# main.net
KiCad netlist of a schematic drawn in EAGLE
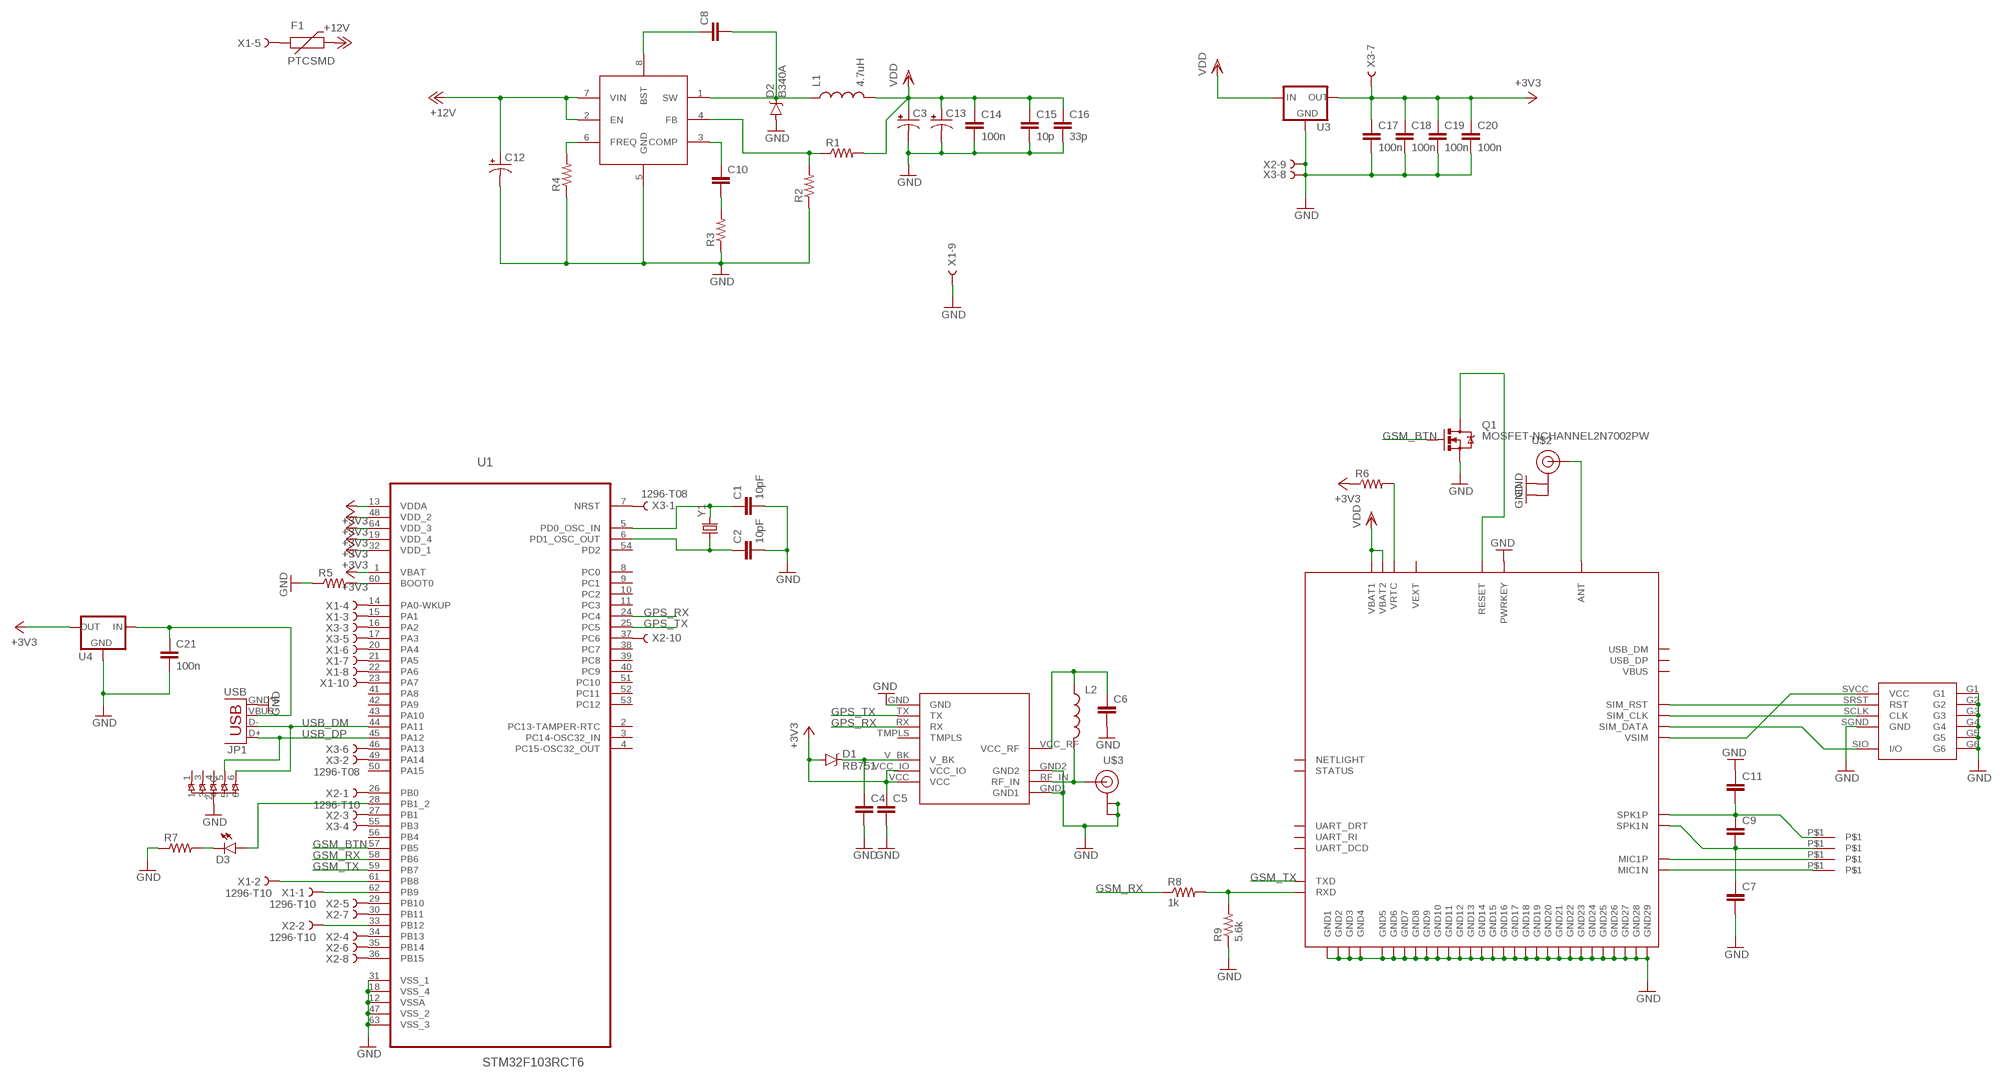
[diagram p0: schematic, sheet 1]

(export (version "E")
  (design (tool "Eeschema 10.0.6"))
  (components
    (comp (ref "C1")
      (value "10pF")
      (footprint "eagle-import:0603-CAP")
      (libsource (lib "eagle-import") (part "10PF-50V-5%(0603)"))
    )
    (comp (ref "C2")
      (value "10pF")
      (footprint "eagle-import:0603-CAP")
      (libsource (lib "eagle-import") (part "10PF-50V-5%(0603)"))
    )
    (comp (ref "C3")
      (value "CAP_POL6032")
      (footprint "eagle-import:EIA6032")
      (libsource (lib "eagle-import") (part "CAP_POL6032"))
    )
    (comp (ref "C4")
      (value "CAP1210")
      (footprint "eagle-import:1210")
      (libsource (lib "eagle-import") (part "CAP1210"))
    )
    (comp (ref "C5")
      (value "CAP1210")
      (footprint "eagle-import:1210")
      (libsource (lib "eagle-import") (part "CAP1210"))
    )
    (comp (ref "C6")
      (value "CAP0402-CAP")
      (footprint "eagle-import:0402-CAP")
      (libsource (lib "eagle-import") (part "SparkFun-Passives_CAP0402-CAP"))
    )
    (comp (ref "C7")
      (value "CAP0402-CAP")
      (footprint "eagle-import:0402-CAP")
      (libsource (lib "eagle-import") (part "SparkFun-Passives_CAP0402-CAP"))
    )
    (comp (ref "C8")
      (value "CAP0805")
      (footprint "eagle-import:0805")
      (libsource (lib "eagle-import") (part "SparkFun-Passives_CAP0805"))
    )
    (comp (ref "C9")
      (value "CAP0402-CAP")
      (footprint "eagle-import:0402-CAP")
      (libsource (lib "eagle-import") (part "SparkFun-Passives_CAP0402-CAP"))
    )
    (comp (ref "C10")
      (value "CAP0402-CAP")
      (footprint "eagle-import:0402-CAP")
      (libsource (lib "eagle-import") (part "SparkFun-Passives_CAP0402-CAP"))
    )
    (comp (ref "C11")
      (value "CAP0402-CAP")
      (footprint "eagle-import:0402-CAP")
      (libsource (lib "eagle-import") (part "SparkFun-Passives_CAP0402-CAP"))
    )
    (comp (ref "C12")
      (value "CPOL-USSMCC")
      (footprint "eagle-import:SMC_C")
      (libsource (lib "eagle-import") (part "CPOL-USSMCC"))
    )
    (comp (ref "C13")
      (value "CAP_POL6032")
      (footprint "eagle-import:EIA6032")
      (libsource (lib "eagle-import") (part "CAP_POL6032"))
    )
    (comp (ref "C14")
      (value "100n")
      (footprint "eagle-import:0805")
      (libsource (lib "eagle-import") (part "SparkFun-Passives_CAP0805"))
    )
    (comp (ref "C15")
      (value "10p")
      (footprint "eagle-import:0402-CAP")
      (libsource (lib "eagle-import") (part "SparkFun-Passives_CAP0402-CAP"))
    )
    (comp (ref "C16")
      (value "33p")
      (footprint "eagle-import:0402-CAP")
      (libsource (lib "eagle-import") (part "SparkFun-Passives_CAP0402-CAP"))
    )
    (comp (ref "C17")
      (value "100n")
      (footprint "eagle-import:0805")
      (libsource (lib "eagle-import") (part "SparkFun-Passives_CAP0805"))
    )
    (comp (ref "C18")
      (value "100n")
      (footprint "eagle-import:0805")
      (libsource (lib "eagle-import") (part "SparkFun-Passives_CAP0805"))
    )
    (comp (ref "C19")
      (value "100n")
      (footprint "eagle-import:0805")
      (libsource (lib "eagle-import") (part "SparkFun-Passives_CAP0805"))
    )
    (comp (ref "C20")
      (value "100n")
      (footprint "eagle-import:0805")
      (libsource (lib "eagle-import") (part "SparkFun-Passives_CAP0805"))
    )
    (comp (ref "C21")
      (value "100n")
      (footprint "eagle-import:0805")
      (libsource (lib "eagle-import") (part "SparkFun-Passives_CAP0805"))
    )
    (comp (ref "D1")
      (value "RB751")
      (footprint "eagle-import:SOD-523")
      (libsource (lib "eagle-import") (part "DIODE-SCHOTTKY-RB751"))
    )
    (comp (ref "D2")
      (value "B340A")
      (footprint "eagle-import:SMA-DIODE")
      (libsource (lib "eagle-import") (part "DIODE-SCHOTTKY-B340A"))
    )
    (comp (ref "D3")
      (value "LED0603")
      (footprint "eagle-import:LED-0603")
      (libsource (lib "eagle-import") (part "LED0603"))
    )
    (comp (ref "F1")
      (value "PTCSMD")
      (footprint "eagle-import:PTC-1206")
      (libsource (lib "eagle-import") (part "PTCSMD"))
    )
    (comp (ref "JP1")
      (value "USB")
      (footprint "eagle-import:USB-MICROB-2")
      (libsource (lib "eagle-import") (part "USB"))
    )
    (comp (ref "L1")
      (value "4.7uH")
      (footprint "eagle-import:CR75")
      (libsource (lib "eagle-import") (part "INDUCTOR68UH-1A"))
    )
    (comp (ref "L2")
      (value "INDUCTOR0402")
      (footprint "eagle-import:C0402")
      (libsource (lib "eagle-import") (part "INDUCTOR0402"))
    )
    (comp (ref "Q1")
      (value "MOSFET-NCHANNEL2N7002PW")
      (footprint "eagle-import:SOT323")
      (libsource (lib "eagle-import") (part "MOSFET-NCHANNEL2N7002PW"))
    )
    (comp (ref "R1")
      (value "RESISTOR0402-RES")
      (footprint "eagle-import:0402-RES")
      (libsource (lib "eagle-import") (part "RESISTOR0402-RES"))
    )
    (comp (ref "R2")
      (value "RESISTOR0402-RES")
      (footprint "eagle-import:0402-RES")
      (libsource (lib "eagle-import") (part "RESISTOR0402-RES"))
    )
    (comp (ref "R3")
      (value "RESISTOR0402-RES")
      (footprint "eagle-import:0402-RES")
      (libsource (lib "eagle-import") (part "RESISTOR0402-RES"))
    )
    (comp (ref "R4")
      (value "RESISTOR0402-RES")
      (footprint "eagle-import:0402-RES")
      (libsource (lib "eagle-import") (part "RESISTOR0402-RES"))
    )
    (comp (ref "R5")
      (value "RESISTOR0402-RES")
      (footprint "eagle-import:0402-RES")
      (libsource (lib "eagle-import") (part "RESISTOR0402-RES"))
    )
    (comp (ref "R6")
      (value "RESISTOR0402-RES")
      (footprint "eagle-import:0402-RES")
      (libsource (lib "eagle-import") (part "RESISTOR0402-RES"))
    )
    (comp (ref "R7")
      (value "RESISTOR0402-RES")
      (footprint "eagle-import:0402-RES")
      (libsource (lib "eagle-import") (part "RESISTOR0402-RES"))
    )
    (comp (ref "R8")
      (value "1k")
      (footprint "eagle-import:0402-RES")
      (libsource (lib "eagle-import") (part "RESISTOR0402-RES"))
    )
    (comp (ref "R9")
      (value "5.6k")
      (footprint "eagle-import:0402-RES")
      (libsource (lib "eagle-import") (part "RESISTOR0402-RES"))
    )
    (comp (ref "U$1")
      (value "SIM800_MIN")
      (footprint "eagle-import:SIM800_MIN")
      (libsource (lib "eagle-import") (part "SIM800_MIN"))
    )
    (comp (ref "U$2")
      (value "U.FL")
      (footprint "eagle-import:U.FL2")
      (libsource (lib "eagle-import") (part "U.FL"))
    )
    (comp (ref "U$3")
      (value "U.FL")
      (footprint "eagle-import:U.FL2")
      (libsource (lib "eagle-import") (part "U.FL"))
    )
    (comp (ref "U$4")
      (value "VK_GPS_U7_MIN")
      (footprint "eagle-import:VK_GPS_U7_MIN")
      (libsource (lib "eagle-import") (part "VK_GPS_U7_MIN"))
    )
    (comp (ref "U$7")
      (value "SIM_NOVPP")
      (footprint "eagle-import:WURTH_NANO_SIM_NOVPP")
      (libsource (lib "eagle-import") (part "SIM_NOVPP"))
    )
    (comp (ref "U$8")
      (value "PAD1")
      (footprint "eagle-import:PAD1")
      (libsource (lib "eagle-import") (part "PAD1"))
    )
    (comp (ref "U$9")
      (value "PAD1")
      (footprint "eagle-import:PAD1")
      (libsource (lib "eagle-import") (part "PAD1"))
    )
    (comp (ref "U$13")
      (value "PAD1")
      (footprint "eagle-import:PAD1")
      (libsource (lib "eagle-import") (part "PAD1"))
    )
    (comp (ref "U$14")
      (value "PAD1")
      (footprint "eagle-import:PAD1")
      (libsource (lib "eagle-import") (part "PAD1"))
    )
    (comp (ref "U1")
      (value "STM32F103RCT6")
      (footprint "eagle-import:QFP50P1200X1200X160-64N")
      (libsource (lib "eagle-import") (part "STM32F103RCT6"))
    )
    (comp (ref "U2")
      (value "MP1584")
      (footprint "eagle-import:SO8")
      (libsource (lib "eagle-import") (part "MP1584"))
    )
    (comp (ref "U3")
      (value "XC63FPM")
      (footprint "eagle-import:SOT23")
      (libsource (lib "eagle-import") (part "XC63FPM"))
    )
    (comp (ref "U4")
      (value "XC63FPM")
      (footprint "eagle-import:SOT23")
      (libsource (lib "eagle-import") (part "XC63FPM"))
    )
    (comp (ref "U5")
      (value "SMF05C")
      (footprint "eagle-import:SC70-6L")
      (libsource (lib "eagle-import") (part "SMF05C"))
    )
    (comp (ref "X1")
      (value "1296-T10")
      (footprint "eagle-import:1296-10")
      (libsource (lib "eagle-import") (part "1296-T10"))
    )
    (comp (ref "X2")
      (value "1296-T10")
      (footprint "eagle-import:1296-10")
      (libsource (lib "eagle-import") (part "1296-T10"))
    )
    (comp (ref "X3")
      (value "1296-T08")
      (footprint "eagle-import:1296-08")
      (libsource (lib "eagle-import") (part "1296-T08"))
    )
    (comp (ref "Y1")
      (value "CRYSTAL5X3")
      (footprint "eagle-import:CRYSTAL-SMD-5X3")
      (libsource (lib "eagle-import") (part "CRYSTAL5X3"))
    )
  )
  (nets
    (net (code "1") (name "+3V3") (class "Default")
      (node (ref "C17") (pin "1") (pinfunction "1_1") (pintype "passive"))
      (node (ref "C18") (pin "1") (pinfunction "1_1") (pintype "passive"))
      (node (ref "C19") (pin "1") (pinfunction "1_1") (pintype "passive"))
      (node (ref "C20") (pin "1") (pinfunction "1_1") (pintype "passive"))
      (node (ref "C5") (pin "1") (pinfunction "1_1") (pintype "passive"))
      (node (ref "D1") (pin "A") (pinfunction "A_A") (pintype "passive"))
      (node (ref "R6") (pin "1") (pinfunction "1_1") (pintype "passive"))
      (node (ref "U$4") (pin "VCC") (pinfunction "VCC_VCC") (pintype "bidirectional"))
      (node (ref "U$4") (pin "VCC_IO") (pinfunction "VCC_IO_VCC_IO") (pintype "bidirectional"))
      (node (ref "U1") (pin "1") (pinfunction "VBAT_1") (pintype "input"))
      (node (ref "U1") (pin "13") (pinfunction "VDDA_13") (pintype "power_in"))
      (node (ref "U1") (pin "19") (pinfunction "VDD_4_19") (pintype "power_in"))
      (node (ref "U1") (pin "32") (pinfunction "VDD_1_32") (pintype "power_in"))
      (node (ref "U1") (pin "48") (pinfunction "VDD_2_48") (pintype "power_in"))
      (node (ref "U1") (pin "64") (pinfunction "VDD_3_64") (pintype "power_in"))
      (node (ref "U3") (pin "2") (pinfunction "OUT_2") (pintype "passive"))
      (node (ref "U4") (pin "2") (pinfunction "OUT_2") (pintype "passive"))
      (node (ref "X3") (pin "7") (pinfunction "B_7") (pintype "passive"))
    )
    (net (code "2") (name "+12V") (class "Default")
      (node (ref "C12") (pin "+") (pinfunction "+_+") (pintype "passive"))
      (node (ref "F1") (pin "2") (pinfunction "2_2") (pintype "bidirectional"))
      (node (ref "U2") (pin "2") (pinfunction "EN_2") (pintype "bidirectional"))
      (node (ref "U2") (pin "7") (pinfunction "VIN_7") (pintype "bidirectional"))
    )
    (net (code "3") (name "/GPS_RX") (class "Default")
      (node (ref "U$4") (pin "RX") (pinfunction "RX_RX") (pintype "bidirectional"))
      (node (ref "U1") (pin "24") (pinfunction "PC4_24") (pintype "passive"))
    )
    (net (code "4") (name "/GPS_TX") (class "Default")
      (node (ref "U$4") (pin "TX") (pinfunction "TX_TX") (pintype "bidirectional"))
      (node (ref "U1") (pin "25") (pinfunction "PC5_25") (pintype "bidirectional"))
    )
    (net (code "5") (name "/GSM_BTN") (class "Default")
      (node (ref "Q1") (pin "1") (pinfunction "G_1") (pintype "passive"))
      (node (ref "U1") (pin "57") (pinfunction "PB5_57") (pintype "bidirectional"))
    )
    (net (code "6") (name "/GSM_RX") (class "Default")
      (node (ref "R8") (pin "1") (pinfunction "1_1") (pintype "passive"))
      (node (ref "U1") (pin "58") (pinfunction "PB6_58") (pintype "bidirectional"))
    )
    (net (code "7") (name "/GSM_TX") (class "Default")
      (node (ref "U$1") (pin "P$32") (pinfunction "TXD_P$32") (pintype "bidirectional"))
      (node (ref "U1") (pin "59") (pinfunction "PB7_59") (pintype "power_in"))
    )
    (net (code "8") (name "/USB_DM") (class "Default")
      (node (ref "JP1") (pin "D-") (pinfunction "D-_D-") (pintype "bidirectional"))
      (node (ref "U1") (pin "44") (pinfunction "PA11_44") (pintype "bidirectional"))
      (node (ref "U5") (pin "6") (pinfunction "6_6") (pintype "bidirectional"))
    )
    (net (code "9") (name "/USB_DP") (class "Default")
      (node (ref "JP1") (pin "D+") (pinfunction "D+_D+") (pintype "bidirectional"))
      (node (ref "U1") (pin "45") (pinfunction "PA12_45") (pintype "bidirectional"))
      (node (ref "U5") (pin "5") (pinfunction "5_5") (pintype "bidirectional"))
    )
    (net (code "10") (name "GND") (class "Default")
      (node (ref "C1") (pin "2") (pinfunction "2_2") (pintype "passive"))
      (node (ref "C11") (pin "1") (pinfunction "1_1") (pintype "passive"))
      (node (ref "C12") (pin "-") (pinfunction "-_-") (pintype "passive"))
      (node (ref "C13") (pin "P$2") (pinfunction "-_P$2") (pintype "passive"))
      (node (ref "C14") (pin "2") (pinfunction "2_2") (pintype "passive"))
      (node (ref "C15") (pin "2") (pinfunction "2_2") (pintype "passive"))
      (node (ref "C16") (pin "2") (pinfunction "2_2") (pintype "passive"))
      (node (ref "C17") (pin "2") (pinfunction "2_2") (pintype "passive"))
      (node (ref "C18") (pin "2") (pinfunction "2_2") (pintype "passive"))
      (node (ref "C19") (pin "2") (pinfunction "2_2") (pintype "passive"))
      (node (ref "C2") (pin "2") (pinfunction "2_2") (pintype "passive"))
      (node (ref "C20") (pin "2") (pinfunction "2_2") (pintype "passive"))
      (node (ref "C21") (pin "2") (pinfunction "2_2") (pintype "passive"))
      (node (ref "C3") (pin "P$2") (pinfunction "-_P$2") (pintype "passive"))
      (node (ref "C4") (pin "2") (pinfunction "2_2") (pintype "passive"))
      (node (ref "C5") (pin "2") (pinfunction "2_2") (pintype "passive"))
      (node (ref "C6") (pin "2") (pinfunction "2_2") (pintype "passive"))
      (node (ref "C7") (pin "2") (pinfunction "2_2") (pintype "passive"))
      (node (ref "D2") (pin "A") (pinfunction "A_A") (pintype "passive"))
      (node (ref "JP1") (pin "GND") (pinfunction "GND_GND") (pintype "bidirectional"))
      (node (ref "JP1") (pin "MT1") (pinfunction "GND_MT1") (pintype "bidirectional"))
      (node (ref "JP1") (pin "MT2") (pinfunction "GND_MT2") (pintype "bidirectional"))
      (node (ref "JP1") (pin "P$1") (pinfunction "GND_P$1") (pintype "bidirectional"))
      (node (ref "JP1") (pin "P$2") (pinfunction "GND_P$2") (pintype "bidirectional"))
      (node (ref "Q1") (pin "2") (pinfunction "S_2") (pintype "passive"))
      (node (ref "R2") (pin "1") (pinfunction "1_1") (pintype "passive"))
      (node (ref "R3") (pin "1") (pinfunction "1_1") (pintype "passive"))
      (node (ref "R4") (pin "1") (pinfunction "1_1") (pintype "passive"))
      (node (ref "R5") (pin "1") (pinfunction "1_1") (pintype "passive"))
      (node (ref "R7") (pin "1") (pinfunction "1_1") (pintype "passive"))
      (node (ref "R9") (pin "1") (pinfunction "1_1") (pintype "passive"))
      (node (ref "U$1") (pin "P$2") (pinfunction "GND1_P$2") (pintype "bidirectional"))
      (node (ref "U$1") (pin "P$35") (pinfunction "GND29_P$35") (pintype "bidirectional"))
      (node (ref "U$1") (pin "P$37") (pinfunction "GND28_P$37") (pintype "bidirectional"))
      (node (ref "U$1") (pin "P$38") (pinfunction "GND27_P$38") (pintype "bidirectional"))
      (node (ref "U$1") (pin "P$39") (pinfunction "GND26_P$39") (pintype "bidirectional"))
      (node (ref "U$1") (pin "P$41") (pinfunction "GND25_P$41") (pintype "bidirectional"))
      (node (ref "U$1") (pin "P$43") (pinfunction "GND22_P$43") (pintype "bidirectional"))
      (node (ref "U$1") (pin "P$44") (pinfunction "GND23_P$44") (pintype "bidirectional"))
      (node (ref "U$1") (pin "P$45") (pinfunction "GND24_P$45") (pintype "bidirectional"))
      (node (ref "U$1") (pin "P$48") (pinfunction "PWRKEY_P$48") (pintype "bidirectional"))
      (node (ref "U$1") (pin "P$58") (pinfunction "GND4_P$58") (pintype "bidirectional"))
      (node (ref "U$1") (pin "P$6") (pinfunction "GND2_P$6") (pintype "bidirectional"))
      (node (ref "U$1") (pin "P$67") (pinfunction "GND17_P$67") (pintype "bidirectional"))
      (node (ref "U$1") (pin "P$71") (pinfunction "GND18_P$71") (pintype "bidirectional"))
      (node (ref "U$1") (pin "P$72") (pinfunction "GND19_P$72") (pintype "bidirectional"))
      (node (ref "U$1") (pin "P$73") (pinfunction "GND20_P$73") (pintype "bidirectional"))
      (node (ref "U$1") (pin "P$76") (pinfunction "GND21_P$76") (pintype "bidirectional"))
      (node (ref "U$1") (pin "P$77") (pinfunction "GND5_P$77") (pintype "bidirectional"))
      (node (ref "U$1") (pin "P$78") (pinfunction "GND6_P$78") (pintype "bidirectional"))
      (node (ref "U$1") (pin "P$79") (pinfunction "GND7_P$79") (pintype "bidirectional"))
      (node (ref "U$1") (pin "P$8") (pinfunction "GND3_P$8") (pintype "bidirectional"))
      (node (ref "U$1") (pin "P$80") (pinfunction "GND8_P$80") (pintype "bidirectional"))
      (node (ref "U$1") (pin "P$81") (pinfunction "GND9_P$81") (pintype "bidirectional"))
      (node (ref "U$1") (pin "P$82") (pinfunction "GND10_P$82") (pintype "bidirectional"))
      (node (ref "U$1") (pin "P$83") (pinfunction "GND11_P$83") (pintype "bidirectional"))
      (node (ref "U$1") (pin "P$84") (pinfunction "GND12_P$84") (pintype "bidirectional"))
      (node (ref "U$1") (pin "P$85") (pinfunction "GND13_P$85") (pintype "bidirectional"))
      (node (ref "U$1") (pin "P$86") (pinfunction "GND14_P$86") (pintype "bidirectional"))
      (node (ref "U$1") (pin "P$87") (pinfunction "GND15_P$87") (pintype "bidirectional"))
      (node (ref "U$1") (pin "P$88") (pinfunction "GND16_P$88") (pintype "bidirectional"))
      (node (ref "U$2") (pin "P$1") (pinfunction "GND_P$1") (pintype "bidirectional"))
      (node (ref "U$2") (pin "P$2") (pinfunction "GND_P$2") (pintype "bidirectional"))
      (node (ref "U$3") (pin "P$1") (pinfunction "GND_P$1") (pintype "bidirectional"))
      (node (ref "U$3") (pin "P$2") (pinfunction "GND_P$2") (pintype "bidirectional"))
      (node (ref "U$4") (pin "GND") (pinfunction "GND_GND") (pintype "bidirectional"))
      (node (ref "U$4") (pin "GND1") (pinfunction "GND1_GND1") (pintype "bidirectional"))
      (node (ref "U$4") (pin "GND2") (pinfunction "GND2_GND2") (pintype "bidirectional"))
      (node (ref "U$7") (pin "G1") (pinfunction "G1_G1") (pintype "bidirectional"))
      (node (ref "U$7") (pin "G2") (pinfunction "G2_G2") (pintype "bidirectional"))
      (node (ref "U$7") (pin "G3") (pinfunction "G3_G3") (pintype "bidirectional"))
      (node (ref "U$7") (pin "G4") (pinfunction "G4_G4") (pintype "bidirectional"))
      (node (ref "U$7") (pin "G5") (pinfunction "G5_G5") (pintype "bidirectional"))
      (node (ref "U$7") (pin "G6") (pinfunction "G6_G6") (pintype "bidirectional"))
      (node (ref "U$7") (pin "SGND") (pinfunction "GND_SGND") (pintype "bidirectional"))
      (node (ref "U1") (pin "12") (pinfunction "VSSA_12") (pintype "passive"))
      (node (ref "U1") (pin "18") (pinfunction "VSS_4_18") (pintype "passive"))
      (node (ref "U1") (pin "31") (pinfunction "VSS_1_31") (pintype "passive"))
      (node (ref "U1") (pin "47") (pinfunction "VSS_2_47") (pintype "passive"))
      (node (ref "U1") (pin "63") (pinfunction "VSS_3_63") (pintype "passive"))
      (node (ref "U2") (pin "5") (pinfunction "GND_5") (pintype "bidirectional"))
      (node (ref "U3") (pin "1") (pinfunction "GND_1") (pintype "input"))
      (node (ref "U4") (pin "1") (pinfunction "GND_1") (pintype "input"))
      (node (ref "U5") (pin "2") (pinfunction "C_2") (pintype "bidirectional"))
      (node (ref "X1") (pin "9") (pinfunction "B_9") (pintype "passive"))
      (node (ref "X2") (pin "9") (pinfunction "B_9") (pintype "passive"))
      (node (ref "X3") (pin "8") (pinfunction "B_8") (pintype "passive"))
    )
    (net (code "11") (name "Net-(C4-Pad1)") (class "Default")
      (node (ref "C4") (pin "1") (pinfunction "1_1") (pintype "passive"))
      (node (ref "D1") (pin "C") (pinfunction "C_C") (pintype "passive"))
      (node (ref "U$4") (pin "V_BK") (pinfunction "V_BK_V_BK") (pintype "bidirectional"))
    )
    (net (code "12") (name "Net-(C6-Pad1)") (class "Default")
      (node (ref "C6") (pin "1") (pinfunction "1_1") (pintype "passive"))
      (node (ref "L2") (pin "1") (pinfunction "1_1") (pintype "passive"))
      (node (ref "U$4") (pin "VCC_RF") (pinfunction "VCC_RF_VCC_RF") (pintype "bidirectional"))
    )
    (net (code "13") (name "Net-(C10-Pad2)") (class "Default")
      (node (ref "C10") (pin "2") (pinfunction "2_2") (pintype "passive"))
      (node (ref "R3") (pin "2") (pinfunction "2_2") (pintype "passive"))
    )
    (net (code "14") (name "Net-(D3-PadC)") (class "Default")
      (node (ref "D3") (pin "C") (pinfunction "C_C") (pintype "passive"))
      (node (ref "R7") (pin "2") (pinfunction "2_2") (pintype "passive"))
    )
    (net (code "15") (name "Net-(L1-1)") (class "Default")
      (node (ref "C8") (pin "2") (pinfunction "2_2") (pintype "passive"))
      (node (ref "D2") (pin "C") (pinfunction "C_C") (pintype "passive"))
      (node (ref "L1") (pin "P$1") (pinfunction "1_P$1") (pintype "passive"))
      (node (ref "U2") (pin "1") (pinfunction "SW_1") (pintype "bidirectional"))
    )
    (net (code "16") (name "Net-(Q1-D)") (class "Default")
      (node (ref "Q1") (pin "3") (pinfunction "D_3") (pintype "passive"))
      (node (ref "U$1") (pin "P$49") (pinfunction "RESET_P$49") (pintype "bidirectional"))
    )
    (net (code "17") (name "Net-(U$1-ANT)") (class "Default")
      (node (ref "U$1") (pin "P$40") (pinfunction "ANT_P$40") (pintype "bidirectional"))
      (node (ref "U$2") (pin "P$3") (pinfunction "SIGNAL_P$3") (pintype "bidirectional"))
    )
    (net (code "18") (name "Net-(U$1-MIC1N)") (class "Default")
      (node (ref "U$1") (pin "P$12") (pinfunction "MIC1N_P$12") (pintype "bidirectional"))
      (node (ref "U$14") (pin "P$1") (pinfunction "P$1_P$1") (pintype "bidirectional"))
    )
    (net (code "19") (name "Net-(U$1-MIC1P)") (class "Default")
      (node (ref "U$1") (pin "P$52") (pinfunction "MIC1P_P$52") (pintype "bidirectional"))
      (node (ref "U$13") (pin "P$1") (pinfunction "P$1_P$1") (pintype "bidirectional"))
    )
    (net (code "20") (name "Net-(U$1-RXD)") (class "Default")
      (node (ref "R8") (pin "2") (pinfunction "2_2") (pintype "passive"))
      (node (ref "R9") (pin "2") (pinfunction "2_2") (pintype "passive"))
      (node (ref "U$1") (pin "P$31") (pinfunction "RXD_P$31") (pintype "bidirectional"))
    )
    (net (code "21") (name "Net-(U$1-SIM_CLK)") (class "Default")
      (node (ref "U$1") (pin "P$55") (pinfunction "SIM_CLK_P$55") (pintype "bidirectional"))
      (node (ref "U$7") (pin "SCLK") (pinfunction "CLK_SCLK") (pintype "bidirectional"))
    )
    (net (code "22") (name "Net-(U$1-SIM_DATA)") (class "Default")
      (node (ref "U$1") (pin "P$14") (pinfunction "SIM_DATA_P$14") (pintype "bidirectional"))
      (node (ref "U$7") (pin "SIO") (pinfunction "I/O_SIO") (pintype "bidirectional"))
    )
    (net (code "23") (name "Net-(U$1-SIM_RST)") (class "Default")
      (node (ref "U$1") (pin "P$15") (pinfunction "SIM_RST_P$15") (pintype "bidirectional"))
      (node (ref "U$7") (pin "SRST") (pinfunction "RST_SRST") (pintype "bidirectional"))
    )
    (net (code "24") (name "Net-(U$1-SPK1N)") (class "Default")
      (node (ref "C7") (pin "1") (pinfunction "1_1") (pintype "passive"))
      (node (ref "C9") (pin "2") (pinfunction "2_2") (pintype "passive"))
      (node (ref "U$1") (pin "P$13") (pinfunction "SPK1N_P$13") (pintype "bidirectional"))
      (node (ref "U$9") (pin "P$1") (pinfunction "P$1_P$1") (pintype "bidirectional"))
    )
    (net (code "25") (name "Net-(U$1-SPK1P)") (class "Default")
      (node (ref "C11") (pin "2") (pinfunction "2_2") (pintype "passive"))
      (node (ref "C9") (pin "1") (pinfunction "1_1") (pintype "passive"))
      (node (ref "U$1") (pin "P$53") (pinfunction "SPK1P_P$53") (pintype "bidirectional"))
      (node (ref "U$8") (pin "P$1") (pinfunction "P$1_P$1") (pintype "bidirectional"))
    )
    (net (code "26") (name "Net-(U$1-VRTC)") (class "Default")
      (node (ref "R6") (pin "2") (pinfunction "2_2") (pintype "passive"))
      (node (ref "U$1") (pin "P$56") (pinfunction "VRTC_P$56") (pintype "bidirectional"))
    )
    (net (code "27") (name "Net-(U$1-VSIM)") (class "Default")
      (node (ref "U$1") (pin "P$16") (pinfunction "VSIM_P$16") (pintype "bidirectional"))
      (node (ref "U$7") (pin "SVCC") (pinfunction "VCC_SVCC") (pintype "bidirectional"))
    )
    (net (code "28") (name "Net-(U$3-SIGNAL)") (class "Default")
      (node (ref "L2") (pin "2") (pinfunction "2_2") (pintype "passive"))
      (node (ref "U$3") (pin "P$3") (pinfunction "SIGNAL_P$3") (pintype "bidirectional"))
      (node (ref "U$4") (pin "RF_IN") (pinfunction "RF_IN_RF_IN") (pintype "bidirectional"))
    )
    (net (code "29") (name "Net-(U1-BOOT0)") (class "Default")
      (node (ref "R5") (pin "2") (pinfunction "2_2") (pintype "passive"))
      (node (ref "U1") (pin "60") (pinfunction "BOOT0_60") (pintype "passive"))
    )
    (net (code "30") (name "Net-(U1-NRST)") (class "Default")
      (node (ref "U1") (pin "7") (pinfunction "NRST_7") (pintype "output"))
      (node (ref "X3") (pin "1") (pinfunction "B_1") (pintype "passive"))
    )
    (net (code "31") (name "Net-(U1-PA0-WKUP)") (class "Default")
      (node (ref "U1") (pin "14") (pinfunction "PA0-WKUP_14") (pintype "bidirectional"))
      (node (ref "X1") (pin "4") (pinfunction "B_4") (pintype "passive"))
    )
    (net (code "32") (name "Net-(U1-PA1)") (class "Default")
      (node (ref "U1") (pin "15") (pinfunction "PA1_15") (pintype "bidirectional"))
      (node (ref "X1") (pin "3") (pinfunction "B_3") (pintype "passive"))
    )
    (net (code "33") (name "Net-(U1-PA2)") (class "Default")
      (node (ref "U1") (pin "16") (pinfunction "PA2_16") (pintype "bidirectional"))
      (node (ref "X3") (pin "3") (pinfunction "B_3") (pintype "passive"))
    )
    (net (code "34") (name "Net-(U1-PA3)") (class "Default")
      (node (ref "U1") (pin "17") (pinfunction "PA3_17") (pintype "bidirectional"))
      (node (ref "X3") (pin "5") (pinfunction "B_5") (pintype "passive"))
    )
    (net (code "35") (name "Net-(U1-PA4)") (class "Default")
      (node (ref "U1") (pin "20") (pinfunction "PA4_20") (pintype "bidirectional"))
      (node (ref "X1") (pin "6") (pinfunction "B_6") (pintype "passive"))
    )
    (net (code "36") (name "Net-(U1-PA5)") (class "Default")
      (node (ref "U1") (pin "21") (pinfunction "PA5_21") (pintype "bidirectional"))
      (node (ref "X1") (pin "7") (pinfunction "B_7") (pintype "passive"))
    )
    (net (code "37") (name "Net-(U1-PA6)") (class "Default")
      (node (ref "U1") (pin "22") (pinfunction "PA6_22") (pintype "bidirectional"))
      (node (ref "X1") (pin "8") (pinfunction "B_8") (pintype "passive"))
    )
    (net (code "38") (name "Net-(U1-PA7)") (class "Default")
      (node (ref "U1") (pin "23") (pinfunction "PA7_23") (pintype "power_in"))
      (node (ref "X1") (pin "10") (pinfunction "B_10") (pintype "passive"))
    )
    (net (code "39") (name "Net-(U1-PA13)") (class "Default")
      (node (ref "U1") (pin "46") (pinfunction "PA13_46") (pintype "bidirectional"))
      (node (ref "X3") (pin "6") (pinfunction "B_6") (pintype "passive"))
    )
    (net (code "40") (name "Net-(U1-PA14)") (class "Default")
      (node (ref "U1") (pin "49") (pinfunction "PA14_49") (pintype "bidirectional"))
      (node (ref "X3") (pin "2") (pinfunction "B_2") (pintype "passive"))
    )
    (net (code "41") (name "Net-(U1-PB0)") (class "Default")
      (node (ref "U1") (pin "26") (pinfunction "PB0_26") (pintype "bidirectional"))
      (node (ref "X2") (pin "1") (pinfunction "B_1") (pintype "passive"))
    )
    (net (code "42") (name "Net-(U1-PB1)") (class "Default")
      (node (ref "U1") (pin "27") (pinfunction "PB1_27") (pintype "bidirectional"))
      (node (ref "X2") (pin "3") (pinfunction "B_3") (pintype "passive"))
    )
    (net (code "43") (name "Net-(U1-PB1_2)") (class "Default")
      (node (ref "D3") (pin "A") (pinfunction "A_A") (pintype "passive"))
      (node (ref "U1") (pin "28") (pinfunction "PB1_2_28") (pintype "bidirectional"))
    )
    (net (code "44") (name "Net-(U1-PB3)") (class "Default")
      (node (ref "U1") (pin "55") (pinfunction "PB3_55") (pintype "bidirectional"))
      (node (ref "X3") (pin "4") (pinfunction "B_4") (pintype "passive"))
    )
    (net (code "45") (name "Net-(U1-PB8)") (class "Default")
      (node (ref "U1") (pin "61") (pinfunction "PB8_61") (pintype "bidirectional"))
      (node (ref "X1") (pin "2") (pinfunction "B_2") (pintype "passive"))
    )
    (net (code "46") (name "Net-(U1-PB9)") (class "Default")
      (node (ref "U1") (pin "62") (pinfunction "PB9_62") (pintype "bidirectional"))
      (node (ref "X1") (pin "1") (pinfunction "B_1") (pintype "passive"))
    )
    (net (code "47") (name "Net-(U1-PB10)") (class "Default")
      (node (ref "U1") (pin "29") (pinfunction "PB10_29") (pintype "bidirectional"))
      (node (ref "X2") (pin "5") (pinfunction "B_5") (pintype "passive"))
    )
    (net (code "48") (name "Net-(U1-PB11)") (class "Default")
      (node (ref "U1") (pin "30") (pinfunction "PB11_30") (pintype "bidirectional"))
      (node (ref "X2") (pin "7") (pinfunction "B_7") (pintype "passive"))
    )
    (net (code "49") (name "Net-(U1-PB12)") (class "Default")
      (node (ref "U1") (pin "33") (pinfunction "PB12_33") (pintype "bidirectional"))
      (node (ref "X2") (pin "2") (pinfunction "B_2") (pintype "passive"))
    )
    (net (code "50") (name "Net-(U1-PB13)") (class "Default")
      (node (ref "U1") (pin "34") (pinfunction "PB13_34") (pintype "bidirectional"))
      (node (ref "X2") (pin "4") (pinfunction "B_4") (pintype "passive"))
    )
    (net (code "51") (name "Net-(U1-PB14)") (class "Default")
      (node (ref "U1") (pin "35") (pinfunction "PB14_35") (pintype "bidirectional"))
      (node (ref "X2") (pin "6") (pinfunction "B_6") (pintype "passive"))
    )
    (net (code "52") (name "Net-(U1-PB15)") (class "Default")
      (node (ref "U1") (pin "36") (pinfunction "PB15_36") (pintype "bidirectional"))
      (node (ref "X2") (pin "8") (pinfunction "B_8") (pintype "passive"))
    )
    (net (code "53") (name "Net-(U1-PC6)") (class "Default")
      (node (ref "U1") (pin "37") (pinfunction "PC6_37") (pintype "bidirectional"))
      (node (ref "X2") (pin "10") (pinfunction "B_10") (pintype "passive"))
    )
    (net (code "54") (name "Net-(U1-PD0_OSC_IN)") (class "Default")
      (node (ref "C1") (pin "1") (pinfunction "1_1") (pintype "passive"))
      (node (ref "U1") (pin "5") (pinfunction "PD0_OSC_IN_5") (pintype "input"))
      (node (ref "Y1") (pin "3") (pinfunction "2_3") (pintype "passive"))
    )
    (net (code "55") (name "Net-(U1-PD1_OSC_OUT)") (class "Default")
      (node (ref "C2") (pin "1") (pinfunction "1_1") (pintype "passive"))
      (node (ref "U1") (pin "6") (pinfunction "PD1_OSC_OUT_6") (pintype "output"))
      (node (ref "Y1") (pin "1") (pinfunction "1_1") (pintype "passive"))
    )
    (net (code "56") (name "Net-(U2-BST)") (class "Default")
      (node (ref "C8") (pin "1") (pinfunction "1_1") (pintype "passive"))
      (node (ref "U2") (pin "8") (pinfunction "BST_8") (pintype "bidirectional"))
    )
    (net (code "57") (name "Net-(U2-COMP)") (class "Default")
      (node (ref "C10") (pin "1") (pinfunction "1_1") (pintype "passive"))
      (node (ref "U2") (pin "3") (pinfunction "COMP_3") (pintype "bidirectional"))
    )
    (net (code "58") (name "Net-(U2-FB)") (class "Default")
      (node (ref "R1") (pin "1") (pinfunction "1_1") (pintype "passive"))
      (node (ref "R2") (pin "2") (pinfunction "2_2") (pintype "passive"))
      (node (ref "U2") (pin "4") (pinfunction "FB_4") (pintype "bidirectional"))
    )
    (net (code "59") (name "Net-(U2-FREQ)") (class "Default")
      (node (ref "R4") (pin "2") (pinfunction "2_2") (pintype "passive"))
      (node (ref "U2") (pin "6") (pinfunction "FREQ_6") (pintype "bidirectional"))
    )
    (net (code "60") (name "Net-(U4-IN)") (class "Default")
      (node (ref "C21") (pin "1") (pinfunction "1_1") (pintype "passive"))
      (node (ref "JP1") (pin "VBUS") (pinfunction "VBUS_VBUS") (pintype "bidirectional"))
      (node (ref "U4") (pin "3") (pinfunction "IN_3") (pintype "input"))
    )
    (net (code "61") (name "Net-(X1F-B)") (class "Default")
      (node (ref "F1") (pin "1") (pinfunction "1_1") (pintype "bidirectional"))
      (node (ref "X1") (pin "5") (pinfunction "B_5") (pintype "passive"))
    )
    (net (code "62") (name "VDD") (class "Default")
      (node (ref "C13") (pin "P$1") (pinfunction "+_P$1") (pintype "passive"))
      (node (ref "C14") (pin "1") (pinfunction "1_1") (pintype "passive"))
      (node (ref "C15") (pin "1") (pinfunction "1_1") (pintype "passive"))
      (node (ref "C16") (pin "1") (pinfunction "1_1") (pintype "passive"))
      (node (ref "C3") (pin "P$1") (pinfunction "+_P$1") (pintype "passive"))
      (node (ref "L1") (pin "P$2") (pinfunction "2_P$2") (pintype "passive"))
      (node (ref "R1") (pin "2") (pinfunction "2_2") (pintype "passive"))
      (node (ref "U$1") (pin "P$1") (pinfunction "VBAT1_P$1") (pintype "bidirectional"))
      (node (ref "U$1") (pin "P$42") (pinfunction "VBAT2_P$42") (pintype "bidirectional"))
      (node (ref "U3") (pin "3") (pinfunction "IN_3") (pintype "input"))
    )
    (net (code "63") (name "unconnected-(U$1-NETLIGHT-PadP$64)") (class "Default")
      (node (ref "U$1") (pin "P$64") (pinfunction "NETLIGHT_P$64") (pintype "bidirectional"))
    )
    (net (code "64") (name "unconnected-(U$1-STATUS-PadP$4)") (class "Default")
      (node (ref "U$1") (pin "P$4") (pinfunction "STATUS_P$4") (pintype "bidirectional"))
    )
    (net (code "65") (name "unconnected-(U$1-UART_DCD-PadP$70)") (class "Default")
      (node (ref "U$1") (pin "P$70") (pinfunction "UART_DCD_P$70") (pintype "bidirectional"))
    )
    (net (code "66") (name "unconnected-(U$1-UART_DRT-PadP$69)") (class "Default")
      (node (ref "U$1") (pin "P$69") (pinfunction "UART_DRT_P$69") (pintype "bidirectional"))
    )
    (net (code "67") (name "unconnected-(U$1-UART_RI-PadP$68)") (class "Default")
      (node (ref "U$1") (pin "P$68") (pinfunction "UART_RI_P$68") (pintype "bidirectional"))
    )
    (net (code "68") (name "unconnected-(U$1-USB_DM-PadP$19)") (class "Default")
      (node (ref "U$1") (pin "P$19") (pinfunction "USB_DM_P$19") (pintype "bidirectional"))
    )
    (net (code "69") (name "unconnected-(U$1-USB_DP-PadP$59)") (class "Default")
      (node (ref "U$1") (pin "P$59") (pinfunction "USB_DP_P$59") (pintype "bidirectional"))
    )
    (net (code "70") (name "unconnected-(U$1-VBUS-PadP$7)") (class "Default")
      (node (ref "U$1") (pin "P$7") (pinfunction "VBUS_P$7") (pintype "bidirectional"))
    )
    (net (code "71") (name "unconnected-(U$1-VEXT-PadP$18)") (class "Default")
      (node (ref "U$1") (pin "P$18") (pinfunction "VEXT_P$18") (pintype "bidirectional"))
    )
    (net (code "72") (name "unconnected-(U$4-PadTMPLS)") (class "Default")
      (node (ref "U$4") (pin "TMPLS") (pinfunction "TMPLS_TMPLS") (pintype "bidirectional"))
    )
    (net (code "73") (name "unconnected-(U1-PA8-Pad41)") (class "Default")
      (node (ref "U1") (pin "41") (pinfunction "PA8_41") (pintype "bidirectional"))
    )
    (net (code "74") (name "unconnected-(U1-PA9-Pad42)") (class "Default")
      (node (ref "U1") (pin "42") (pinfunction "PA9_42") (pintype "bidirectional"))
    )
    (net (code "75") (name "unconnected-(U1-PA10-Pad43)") (class "Default")
      (node (ref "U1") (pin "43") (pinfunction "PA10_43") (pintype "bidirectional"))
    )
    (net (code "76") (name "unconnected-(U1-PA15-Pad50)") (class "Default")
      (node (ref "U1") (pin "50") (pinfunction "PA15_50") (pintype "bidirectional"))
    )
    (net (code "77") (name "unconnected-(U1-PB4-Pad56)") (class "Default")
      (node (ref "U1") (pin "56") (pinfunction "PB4_56") (pintype "bidirectional"))
    )
    (net (code "78") (name "unconnected-(U1-PC0-Pad8)") (class "Default")
      (node (ref "U1") (pin "8") (pinfunction "PC0_8") (pintype "bidirectional"))
    )
    (net (code "79") (name "unconnected-(U1-PC1-Pad9)") (class "Default")
      (node (ref "U1") (pin "9") (pinfunction "PC1_9") (pintype "bidirectional"))
    )
    (net (code "80") (name "unconnected-(U1-PC2-Pad10)") (class "Default")
      (node (ref "U1") (pin "10") (pinfunction "PC2_10") (pintype "bidirectional"))
    )
    (net (code "81") (name "unconnected-(U1-PC3-Pad11)") (class "Default")
      (node (ref "U1") (pin "11") (pinfunction "PC3_11") (pintype "bidirectional"))
    )
    (net (code "82") (name "unconnected-(U1-PC7-Pad38)") (class "Default")
      (node (ref "U1") (pin "38") (pinfunction "PC7_38") (pintype "bidirectional"))
    )
    (net (code "83") (name "unconnected-(U1-PC8-Pad39)") (class "Default")
      (node (ref "U1") (pin "39") (pinfunction "PC8_39") (pintype "bidirectional"))
    )
    (net (code "84") (name "unconnected-(U1-PC9-Pad40)") (class "Default")
      (node (ref "U1") (pin "40") (pinfunction "PC9_40") (pintype "bidirectional"))
    )
    (net (code "85") (name "unconnected-(U1-PC10-Pad51)") (class "Default")
      (node (ref "U1") (pin "51") (pinfunction "PC10_51") (pintype "bidirectional"))
    )
    (net (code "86") (name "unconnected-(U1-PC11-Pad52)") (class "Default")
      (node (ref "U1") (pin "52") (pinfunction "PC11_52") (pintype "bidirectional"))
    )
    (net (code "87") (name "unconnected-(U1-PC12-Pad53)") (class "Default")
      (node (ref "U1") (pin "53") (pinfunction "PC12_53") (pintype "bidirectional"))
    )
    (net (code "88") (name "unconnected-(U1-PC13-TAMPER-RTC-Pad2)") (class "Default")
      (node (ref "U1") (pin "2") (pinfunction "PC13-TAMPER-RTC_2") (pintype "input"))
    )
    (net (code "89") (name "unconnected-(U1-PC14-OSC32_IN-Pad3)") (class "Default")
      (node (ref "U1") (pin "3") (pinfunction "PC14-OSC32_IN_3") (pintype "input"))
    )
    (net (code "90") (name "unconnected-(U1-PC15-OSC32_OUT-Pad4)") (class "Default")
      (node (ref "U1") (pin "4") (pinfunction "PC15-OSC32_OUT_4") (pintype "output"))
    )
    (net (code "91") (name "unconnected-(U1-PD2-Pad54)") (class "Default")
      (node (ref "U1") (pin "54") (pinfunction "PD2_54") (pintype "bidirectional"))
    )
    (net (code "92") (name "unconnected-(U5-Pad1)") (class "Default")
      (node (ref "U5") (pin "1") (pinfunction "1_1") (pintype "bidirectional"))
    )
    (net (code "93") (name "unconnected-(U5-Pad3)") (class "Default")
      (node (ref "U5") (pin "3") (pinfunction "3_3") (pintype "bidirectional"))
    )
    (net (code "94") (name "unconnected-(U5-Pad4)") (class "Default")
      (node (ref "U5") (pin "4") (pinfunction "4_4") (pintype "bidirectional"))
    )
  )
)
